# mapleCUx_med_024.net
KiCad netlist of a schematic drawn in EAGLE
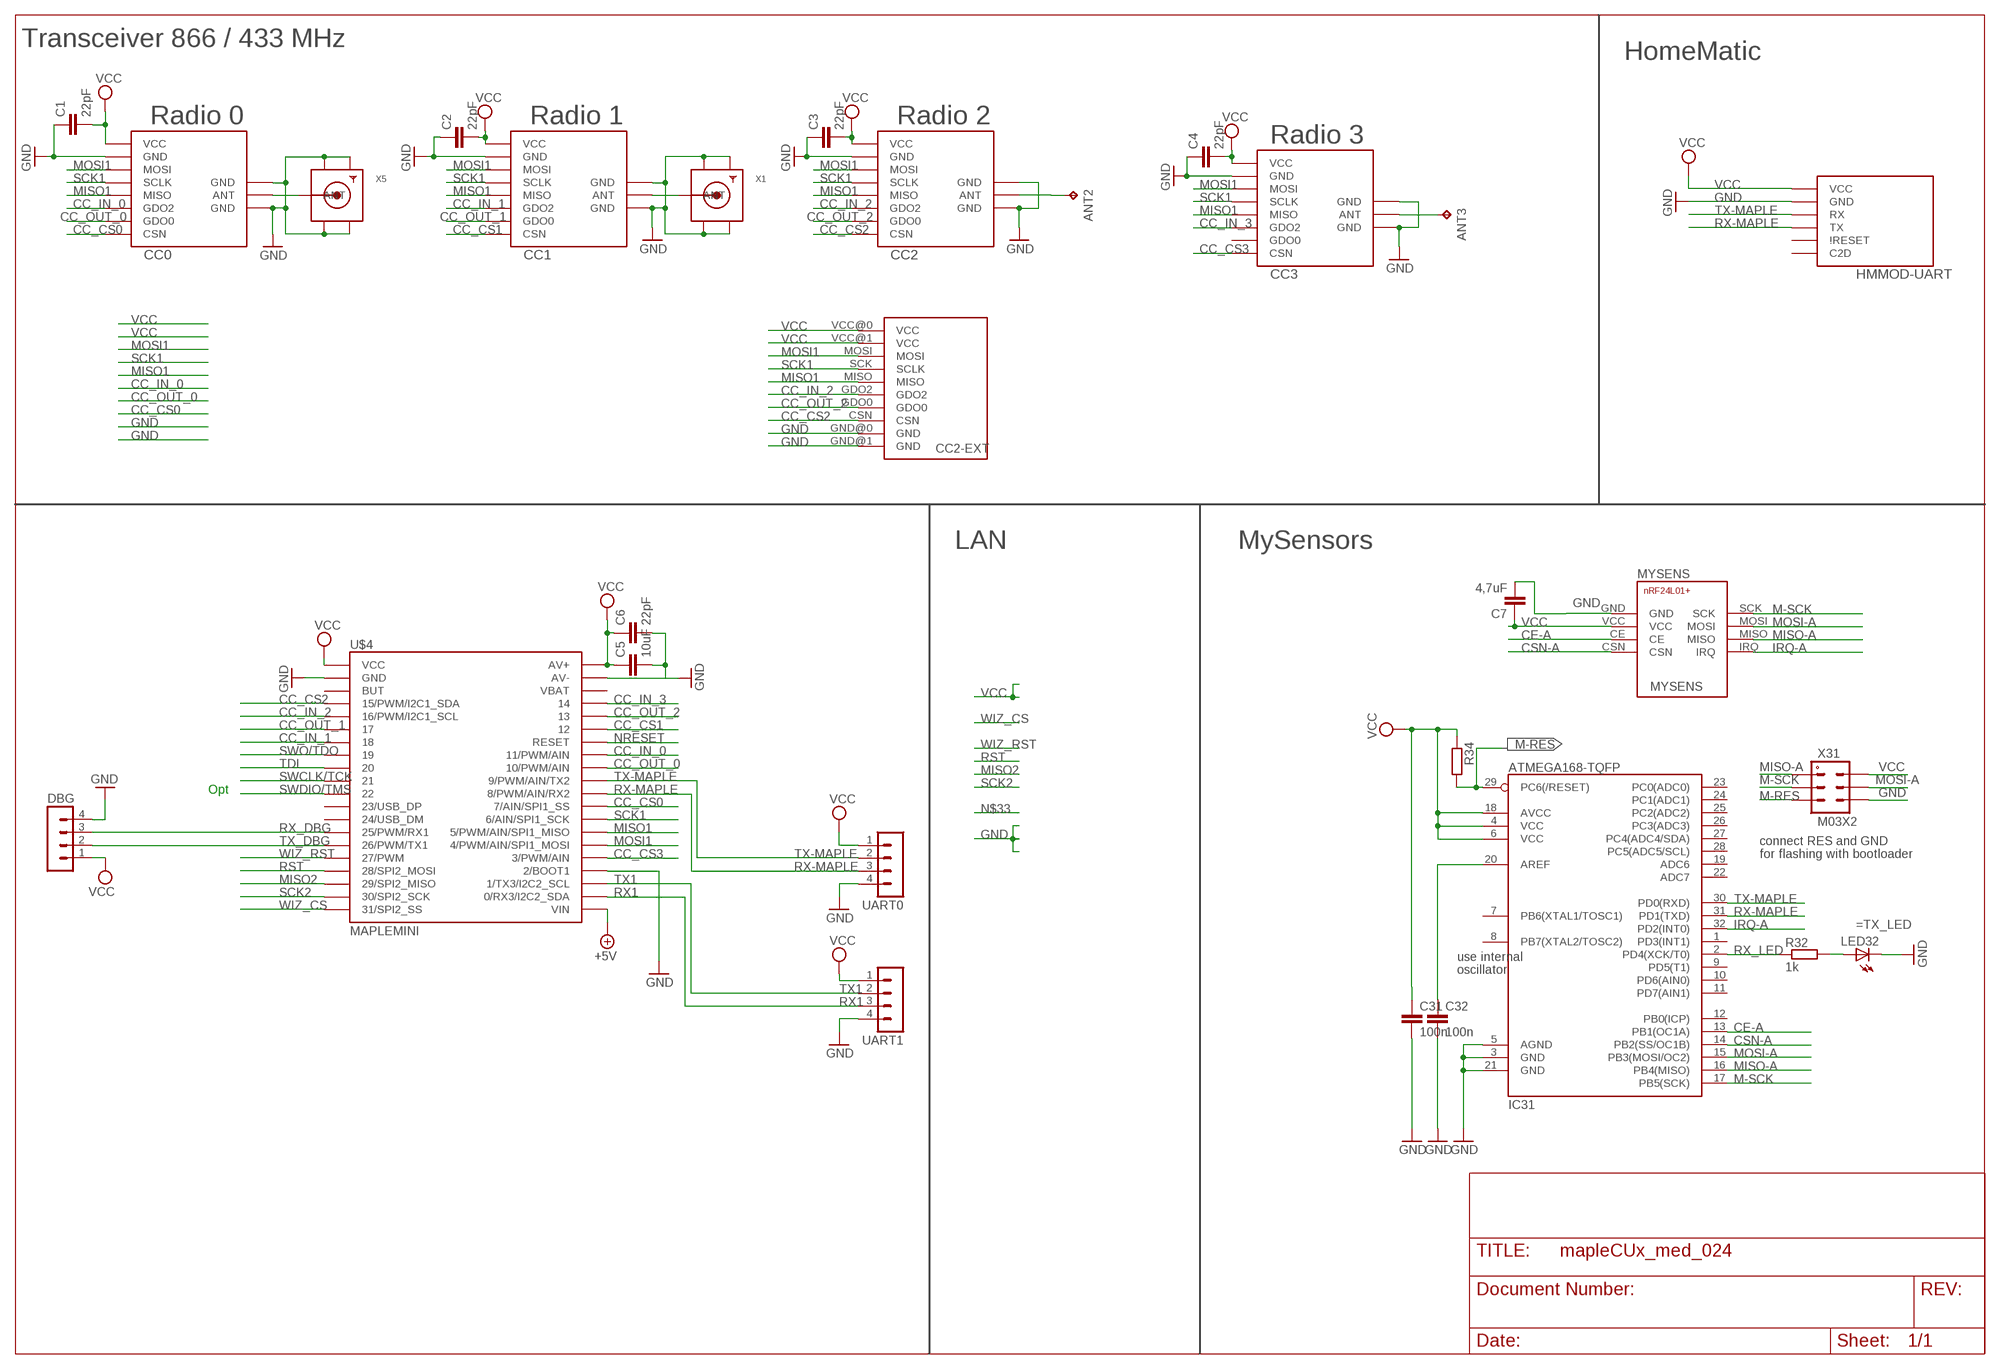
[diagram p0: schematic, sheet 1]

(export (version "E")
  (design (tool "Eeschema 10.0.6"))
  (components
    (comp (ref "ANT2")
      (value "TPPAD1-13")
      (footprint "eagle-import:P1-13")
      (libsource (lib "eagle-import") (part "TPPAD1-13"))
    )
    (comp (ref "ANT3")
      (value "TPPAD1-13")
      (footprint "eagle-import:P1-13")
      (libsource (lib "eagle-import") (part "TPPAD1-13"))
    )
    (comp (ref "C1")
      (value "22pF")
      (footprint "eagle-import:C0805")
      (libsource (lib "eagle-import") (part "C-EUC0805"))
    )
    (comp (ref "C2")
      (value "22pF")
      (footprint "eagle-import:C0805")
      (libsource (lib "eagle-import") (part "C-EUC0805"))
    )
    (comp (ref "C3")
      (value "22pF")
      (footprint "eagle-import:C0805")
      (libsource (lib "eagle-import") (part "C-EUC0805"))
    )
    (comp (ref "C4")
      (value "22pF")
      (footprint "eagle-import:C0805")
      (libsource (lib "eagle-import") (part "C-EUC0805"))
    )
    (comp (ref "C5")
      (value "10uF")
      (footprint "eagle-import:C1210")
      (libsource (lib "eagle-import") (part "C-EUC1210"))
    )
    (comp (ref "C6")
      (value "22pF")
      (footprint "eagle-import:C0805")
      (libsource (lib "eagle-import") (part "C-EUC0805"))
    )
    (comp (ref "C7")
      (value "4,7uF")
      (footprint "eagle-import:C1210")
      (libsource (lib "eagle-import") (part "C-EUC1210"))
    )
    (comp (ref "C31")
      (value "100n")
      (footprint "eagle-import:C0805")
      (libsource (lib "eagle-import") (part "C-EUC0805"))
    )
    (comp (ref "C32")
      (value "100n")
      (footprint "eagle-import:C0805")
      (libsource (lib "eagle-import") (part "C-EUC0805"))
    )
    (comp (ref "CC0")
      (value "CC1101")
      (footprint "eagle-import:CC1101_MODULE1_SMD")
      (libsource (lib "eagle-import") (part "CC1101_MODULE1SMD"))
    )
    (comp (ref "CC1")
      (value "CC1101_MODULE1SMD")
      (footprint "eagle-import:CC1101_MODULE1_SMD")
      (libsource (lib "eagle-import") (part "CC1101_MODULE1SMD"))
    )
    (comp (ref "CC2")
      (value "CC1101_MODULE1SMD")
      (footprint "eagle-import:CC1101_MODULE1_SMD")
      (libsource (lib "eagle-import") (part "CC1101_MODULE1SMD"))
    )
    (comp (ref "CC2-EXT")
      (value "CC1101_MODULE3_DIL")
      (footprint "eagle-import:CC1101_MODULE3_DIL")
      (libsource (lib "eagle-import") (part "CC1101_MODULE3_DIL"))
    )
    (comp (ref "CC3")
      (value "CC1101_MODULE1SMD")
      (footprint "eagle-import:CC1101_MODULE1_SMD")
      (libsource (lib "eagle-import") (part "CC1101_MODULE1SMD"))
    )
    (comp (ref "DBG")
      (value "MA04-1")
      (footprint "eagle-import:MA04-1")
      (libsource (lib "eagle-import") (part "MA04-1"))
    )
    (comp (ref "HMMOD-UART")
      (value "HM-MOD-UARTDIL")
      (footprint "eagle-import:HM-MOD-UART-DIL")
      (libsource (lib "eagle-import") (part "HM-MOD-UARTDIL"))
    )
    (comp (ref "IC31")
      (value "ATMEGA168-TQFP")
      (footprint "eagle-import:TQFP32-08")
      (libsource (lib "eagle-import") (part "ATMEGA168-TQFP"))
    )
    (comp (ref "LED32")
      (value "LEDCHIPLED_0805")
      (footprint "eagle-import:CHIPLED_0805")
      (libsource (lib "eagle-import") (part "LEDCHIPLED_0805"))
    )
    (comp (ref "MYSENS")
      (value "NRF24L01+SMD")
      (footprint "eagle-import:NRF24L01+SMD")
      (libsource (lib "eagle-import") (part "NRF24L01+SMD"))
    )
    (comp (ref "R32")
      (value "1k")
      (footprint "eagle-import:R0805")
      (libsource (lib "eagle-import") (part "R-EU_R0805"))
    )
    (comp (ref "R34")
      (value "R-EU_R0805")
      (footprint "eagle-import:R0805")
      (libsource (lib "eagle-import") (part "R-EU_R0805"))
    )
    (comp (ref "U$4")
      (value "MAPLEMINI")
      (footprint "eagle-import:20-DIP")
      (libsource (lib "eagle-import") (part "MAPLEMINI"))
    )
    (comp (ref "UART0")
      (value "MA04-1")
      (footprint "eagle-import:MA04-1")
      (libsource (lib "eagle-import") (part "MA04-1"))
    )
    (comp (ref "UART1")
      (value "MA04-1")
      (footprint "eagle-import:MA04-1")
      (libsource (lib "eagle-import") (part "MA04-1"))
    )
    (comp (ref "X1")
      (value "SMACONNECTOR_EDGE_UFL")
      (footprint "eagle-import:SMA_EDGELAUNCH_UFL")
      (libsource (lib "eagle-import") (part "SMACONNECTOR_EDGE_UFL"))
    )
    (comp (ref "X5")
      (value "SMACONNECTOR_EDGE_UFL")
      (footprint "eagle-import:SMA_EDGELAUNCH_UFL")
      (libsource (lib "eagle-import") (part "SMACONNECTOR_EDGE_UFL"))
    )
    (comp (ref "X31")
      (value "M03X2")
      (footprint "eagle-import:2X03-1.27MM_SMD")
      (libsource (lib "eagle-import") (part "M03X2"))
    )
  )
  (nets
    (net (code "1") (name "+5V") (class "Default")
      (node (ref "U$4") (pin "21") (pinfunction "VIN_21") (pintype "bidirectional"))
    )
    (net (code "2") (name "/CC_CS0") (class "Default")
      (node (ref "CC0") (pin "CSN") (pinfunction "CSN_CSN") (pintype "bidirectional"))
      (node (ref "U$4") (pin "29") (pinfunction "7/AIN/SPI1_SS_29") (pintype "bidirectional"))
    )
    (net (code "3") (name "/CC_CS1") (class "Default")
      (node (ref "CC1") (pin "CSN") (pinfunction "CSN_CSN") (pintype "bidirectional"))
      (node (ref "U$4") (pin "35") (pinfunction "12_35") (pintype "bidirectional"))
    )
    (net (code "4") (name "/CC_CS2") (class "Default")
      (node (ref "CC2") (pin "CSN") (pinfunction "CSN_CSN") (pintype "bidirectional"))
      (node (ref "CC2-EXT") (pin "CSN") (pinfunction "CSN_CSN") (pintype "bidirectional"))
      (node (ref "U$4") (pin "4") (pinfunction "15/PWM/I2C1_SDA_4") (pintype "bidirectional"))
    )
    (net (code "5") (name "/CC_CS3") (class "Default")
      (node (ref "CC3") (pin "CSN") (pinfunction "CSN_CSN") (pintype "bidirectional"))
      (node (ref "U$4") (pin "25") (pinfunction "3/PWM/AIN_25") (pintype "bidirectional"))
    )
    (net (code "6") (name "/CC_IN_0") (class "Default")
      (node (ref "CC0") (pin "GDO2") (pinfunction "GDO2_GDO2") (pintype "bidirectional"))
      (node (ref "U$4") (pin "33") (pinfunction "11/PWM/AIN_33") (pintype "bidirectional"))
    )
    (net (code "7") (name "/CC_IN_1") (class "Default")
      (node (ref "CC1") (pin "GDO2") (pinfunction "GDO2_GDO2") (pintype "bidirectional"))
      (node (ref "U$4") (pin "7") (pinfunction "18_7") (pintype "bidirectional"))
    )
    (net (code "8") (name "/CC_IN_2") (class "Default")
      (node (ref "CC2") (pin "GDO2") (pinfunction "GDO2_GDO2") (pintype "bidirectional"))
      (node (ref "CC2-EXT") (pin "GDO2") (pinfunction "GDO2_GDO2") (pintype "bidirectional"))
      (node (ref "U$4") (pin "5") (pinfunction "16/PWM/I2C1_SCL_5") (pintype "bidirectional"))
    )
    (net (code "9") (name "/CC_IN_3") (class "Default")
      (node (ref "CC3") (pin "GDO2") (pinfunction "GDO2_GDO2") (pintype "bidirectional"))
      (node (ref "U$4") (pin "37") (pinfunction "14_37") (pintype "bidirectional"))
    )
    (net (code "10") (name "/CC_OUT_0") (class "Default")
      (node (ref "CC0") (pin "GDO0") (pinfunction "GDO0_GDO0") (pintype "bidirectional"))
      (node (ref "U$4") (pin "32") (pinfunction "10/PWM/AIN_32") (pintype "bidirectional"))
    )
    (net (code "11") (name "/CC_OUT_1") (class "Default")
      (node (ref "CC1") (pin "GDO0") (pinfunction "GDO0_GDO0") (pintype "bidirectional"))
      (node (ref "U$4") (pin "6") (pinfunction "17_6") (pintype "bidirectional"))
    )
    (net (code "12") (name "/CC_OUT_2") (class "Default")
      (node (ref "CC2") (pin "GDO0") (pinfunction "GDO0_GDO0") (pintype "bidirectional"))
      (node (ref "CC2-EXT") (pin "GDO0") (pinfunction "GDO0_GDO0") (pintype "bidirectional"))
      (node (ref "U$4") (pin "36") (pinfunction "13_36") (pintype "bidirectional"))
    )
    (net (code "13") (name "/CE-A") (class "Default")
      (node (ref "IC31") (pin "13") (pinfunction "PB1(OC1A)_13") (pintype "bidirectional"))
      (node (ref "MYSENS") (pin "CE") (pinfunction "CE_CE") (pintype "bidirectional"))
    )
    (net (code "14") (name "/CSN-A") (class "Default")
      (node (ref "IC31") (pin "14") (pinfunction "PB2(SS/OC1B)_14") (pintype "bidirectional"))
      (node (ref "MYSENS") (pin "CSN") (pinfunction "CSN_CSN") (pintype "bidirectional"))
    )
    (net (code "15") (name "/IRQ-A") (class "Default")
      (node (ref "IC31") (pin "32") (pinfunction "PD2(INT0)_32") (pintype "bidirectional"))
      (node (ref "MYSENS") (pin "IRQ") (pinfunction "IRQ_IRQ") (pintype "bidirectional"))
    )
    (net (code "16") (name "/M-RES") (class "Default")
      (node (ref "IC31") (pin "29") (pinfunction "PC6(/RESET)_29") (pintype "bidirectional"))
      (node (ref "R34") (pin "2") (pinfunction "2_2") (pintype "passive"))
      (node (ref "X31") (pin "P$5") (pinfunction "5_P$5") (pintype "passive"))
    )
    (net (code "17") (name "/M-SCK") (class "Default")
      (node (ref "IC31") (pin "17") (pinfunction "PB5(SCK)_17") (pintype "bidirectional"))
      (node (ref "MYSENS") (pin "SCK") (pinfunction "SCK_SCK") (pintype "bidirectional"))
      (node (ref "X31") (pin "P$3") (pinfunction "3_P$3") (pintype "passive"))
    )
    (net (code "18") (name "/MISO-A") (class "Default")
      (node (ref "IC31") (pin "16") (pinfunction "PB4(MISO)_16") (pintype "bidirectional"))
      (node (ref "MYSENS") (pin "MISO") (pinfunction "MISO_MISO") (pintype "bidirectional"))
      (node (ref "X31") (pin "P$1") (pinfunction "1_P$1") (pintype "passive"))
    )
    (net (code "19") (name "/MISO1") (class "Default")
      (node (ref "CC0") (pin "MISO") (pinfunction "MISO_MISO") (pintype "bidirectional"))
      (node (ref "CC1") (pin "MISO") (pinfunction "MISO_MISO") (pintype "bidirectional"))
      (node (ref "CC2") (pin "MISO") (pinfunction "MISO_MISO") (pintype "bidirectional"))
      (node (ref "CC2-EXT") (pin "MISO") (pinfunction "MISO_MISO") (pintype "bidirectional"))
      (node (ref "CC3") (pin "MISO") (pinfunction "MISO_MISO") (pintype "bidirectional"))
      (node (ref "U$4") (pin "27") (pinfunction "5/PWM/AIN/SPI1_MISO_27") (pintype "bidirectional"))
    )
    (net (code "20") (name "/MISO2") (class "Default")
      (node (ref "U$4") (pin "18") (pinfunction "29/SPI2_MISO_18") (pintype "bidirectional"))
    )
    (net (code "21") (name "/MOSI-A") (class "Default")
      (node (ref "IC31") (pin "15") (pinfunction "PB3(MOSI/OC2)_15") (pintype "bidirectional"))
      (node (ref "MYSENS") (pin "MOSI") (pinfunction "MOSI_MOSI") (pintype "bidirectional"))
      (node (ref "X31") (pin "P$4") (pinfunction "4_P$4") (pintype "passive"))
    )
    (net (code "22") (name "/MOSI1") (class "Default")
      (node (ref "CC0") (pin "MOSI") (pinfunction "MOSI_MOSI") (pintype "bidirectional"))
      (node (ref "CC1") (pin "MOSI") (pinfunction "MOSI_MOSI") (pintype "bidirectional"))
      (node (ref "CC2") (pin "MOSI") (pinfunction "MOSI_MOSI") (pintype "bidirectional"))
      (node (ref "CC2-EXT") (pin "MOSI") (pinfunction "MOSI_MOSI") (pintype "bidirectional"))
      (node (ref "CC3") (pin "MOSI") (pinfunction "MOSI_MOSI") (pintype "bidirectional"))
      (node (ref "U$4") (pin "26") (pinfunction "4/PWM/AIN/SPI1_MOSI_26") (pintype "bidirectional"))
    )
    (net (code "24") (name "/NRESET") (class "Default")
      (node (ref "U$4") (pin "34") (pinfunction "RESET_34") (pintype "bidirectional"))
    )
    (net (code "25") (name "/RST") (class "Default")
      (node (ref "U$4") (pin "17") (pinfunction "28/SPI2_MOSI_17") (pintype "bidirectional"))
    )
    (net (code "26") (name "/RX-MAPLE") (class "Default")
      (node (ref "HMMOD-UART") (pin "5") (pinfunction "TX_5") (pintype "bidirectional"))
      (node (ref "IC31") (pin "31") (pinfunction "PD1(TXD)_31") (pintype "bidirectional"))
      (node (ref "U$4") (pin "30") (pinfunction "8/PWM/AIN/RX2_30") (pintype "bidirectional"))
      (node (ref "UART0") (pin "3") (pinfunction "3_3") (pintype "passive"))
    )
    (net (code "27") (name "/RX1") (class "Default")
      (node (ref "U$4") (pin "22") (pinfunction "0/RX3/I2C2_SDA_22") (pintype "bidirectional"))
      (node (ref "UART1") (pin "3") (pinfunction "3_3") (pintype "passive"))
    )
    (net (code "28") (name "/RX_DBG") (class "Default")
      (node (ref "DBG") (pin "3") (pinfunction "3_3") (pintype "passive"))
      (node (ref "U$4") (pin "14") (pinfunction "25/PWM/RX1_14") (pintype "bidirectional"))
    )
    (net (code "29") (name "/RX_LED") (class "Default")
      (node (ref "IC31") (pin "2") (pinfunction "PD4(XCK/T0)_2") (pintype "bidirectional"))
      (node (ref "R32") (pin "1") (pinfunction "1_1") (pintype "passive"))
    )
    (net (code "30") (name "/SCK1") (class "Default")
      (node (ref "CC0") (pin "SCLK") (pinfunction "SCLK_SCLK") (pintype "bidirectional"))
      (node (ref "CC1") (pin "SCLK") (pinfunction "SCLK_SCLK") (pintype "bidirectional"))
      (node (ref "CC2") (pin "SCLK") (pinfunction "SCLK_SCLK") (pintype "bidirectional"))
      (node (ref "CC2-EXT") (pin "SCK") (pinfunction "SCLK_SCK") (pintype "bidirectional"))
      (node (ref "CC3") (pin "SCLK") (pinfunction "SCLK_SCLK") (pintype "bidirectional"))
      (node (ref "U$4") (pin "28") (pinfunction "6/AIN/SPI1_SCK_28") (pintype "bidirectional"))
    )
    (net (code "31") (name "/SCK2") (class "Default")
      (node (ref "U$4") (pin "19") (pinfunction "30/SPI2_SCK_19") (pintype "bidirectional"))
    )
    (net (code "32") (name "/SWCLK{slash}TCK") (class "Default")
      (node (ref "U$4") (pin "10") (pinfunction "21_10") (pintype "bidirectional"))
    )
    (net (code "33") (name "/SWDIO{slash}TMS") (class "Default")
      (node (ref "U$4") (pin "11") (pinfunction "22_11") (pintype "bidirectional"))
    )
    (net (code "34") (name "/SWO{slash}TDO") (class "Default")
      (node (ref "U$4") (pin "8") (pinfunction "19_8") (pintype "bidirectional"))
    )
    (net (code "35") (name "/TDI") (class "Default")
      (node (ref "U$4") (pin "9") (pinfunction "20_9") (pintype "bidirectional"))
    )
    (net (code "36") (name "/TX-MAPLE") (class "Default")
      (node (ref "HMMOD-UART") (pin "6") (pinfunction "RX_6") (pintype "bidirectional"))
      (node (ref "IC31") (pin "30") (pinfunction "PD0(RXD)_30") (pintype "bidirectional"))
      (node (ref "U$4") (pin "31") (pinfunction "9/PWM/AIN/TX2_31") (pintype "bidirectional"))
      (node (ref "UART0") (pin "2") (pinfunction "2_2") (pintype "passive"))
    )
    (net (code "37") (name "/TX1") (class "Default")
      (node (ref "U$4") (pin "23") (pinfunction "1/TX3/I2C2_SCL_23") (pintype "bidirectional"))
      (node (ref "UART1") (pin "2") (pinfunction "2_2") (pintype "passive"))
    )
    (net (code "38") (name "/TX_DBG") (class "Default")
      (node (ref "DBG") (pin "2") (pinfunction "2_2") (pintype "passive"))
      (node (ref "U$4") (pin "15") (pinfunction "26/PWM/TX1_15") (pintype "bidirectional"))
    )
    (net (code "39") (name "/WIZ_CS") (class "Default")
      (node (ref "U$4") (pin "20") (pinfunction "31/SPI2_SS_20") (pintype "bidirectional"))
    )
    (net (code "40") (name "/WIZ_RST") (class "Default")
      (node (ref "U$4") (pin "16") (pinfunction "27/PWM_16") (pintype "bidirectional"))
    )
    (net (code "41") (name "GND") (class "Default")
      (node (ref "C1") (pin "1") (pinfunction "1_1") (pintype "passive"))
      (node (ref "C2") (pin "1") (pinfunction "1_1") (pintype "passive"))
      (node (ref "C3") (pin "1") (pinfunction "1_1") (pintype "passive"))
      (node (ref "C31") (pin "2") (pinfunction "2_2") (pintype "passive"))
      (node (ref "C32") (pin "2") (pinfunction "2_2") (pintype "passive"))
      (node (ref "C4") (pin "1") (pinfunction "1_1") (pintype "passive"))
      (node (ref "C5") (pin "2") (pinfunction "2_2") (pintype "passive"))
      (node (ref "C6") (pin "2") (pinfunction "2_2") (pintype "passive"))
      (node (ref "C7") (pin "2") (pinfunction "2_2") (pintype "passive"))
      (node (ref "CC0") (pin "GND@0") (pinfunction "GND_GND@0") (pintype "power_in"))
      (node (ref "CC0") (pin "GND@1") (pinfunction "GND_GND@1") (pintype "power_in"))
      (node (ref "CC0") (pin "GND@2") (pinfunction "GND_GND@2") (pintype "power_in"))
      (node (ref "CC1") (pin "GND@0") (pinfunction "GND_GND@0") (pintype "power_in"))
      (node (ref "CC1") (pin "GND@1") (pinfunction "GND_GND@1") (pintype "power_in"))
      (node (ref "CC1") (pin "GND@2") (pinfunction "GND_GND@2") (pintype "power_in"))
      (node (ref "CC2") (pin "GND@0") (pinfunction "GND_GND@0") (pintype "power_in"))
      (node (ref "CC2") (pin "GND@1") (pinfunction "GND_GND@1") (pintype "power_in"))
      (node (ref "CC2") (pin "GND@2") (pinfunction "GND_GND@2") (pintype "power_in"))
      (node (ref "CC2-EXT") (pin "GND@0") (pinfunction "GND_GND@0") (pintype "power_in"))
      (node (ref "CC2-EXT") (pin "GND@1") (pinfunction "GND_GND@1") (pintype "power_in"))
      (node (ref "CC3") (pin "GND@0") (pinfunction "GND_GND@0") (pintype "power_in"))
      (node (ref "CC3") (pin "GND@1") (pinfunction "GND_GND@1") (pintype "power_in"))
      (node (ref "CC3") (pin "GND@2") (pinfunction "GND_GND@2") (pintype "power_in"))
      (node (ref "DBG") (pin "4") (pinfunction "4_4") (pintype "passive"))
      (node (ref "HMMOD-UART") (pin "2") (pinfunction "GND_2") (pintype "power_in"))
      (node (ref "IC31") (pin "21") (pinfunction "GND_21") (pintype "bidirectional"))
      (node (ref "IC31") (pin "3") (pinfunction "GND_3") (pintype "bidirectional"))
      (node (ref "IC31") (pin "5") (pinfunction "AGND_5") (pintype "bidirectional"))
      (node (ref "LED32") (pin "C") (pinfunction "C_C") (pintype "passive"))
      (node (ref "MYSENS") (pin "GND") (pinfunction "GND_GND") (pintype "power_in"))
      (node (ref "U$4") (pin "2") (pinfunction "GND_2") (pintype "bidirectional"))
      (node (ref "U$4") (pin "24") (pinfunction "2/BOOT1_24") (pintype "bidirectional"))
      (node (ref "U$4") (pin "39") (pinfunction "AV-_39") (pintype "bidirectional"))
      (node (ref "UART0") (pin "4") (pinfunction "4_4") (pintype "passive"))
      (node (ref "UART1") (pin "4") (pinfunction "4_4") (pintype "passive"))
      (node (ref "X1") (pin "GND@1") (pinfunction "GND1_GND@1") (pintype "power_in"))
      (node (ref "X1") (pin "GND@2") (pinfunction "GND2_GND@2") (pintype "power_in"))
      (node (ref "X1") (pin "GND@3") (pinfunction "GND3_GND@3") (pintype "power_in"))
      (node (ref "X1") (pin "GND@4") (pinfunction "GND4_GND@4") (pintype "power_in"))
      (node (ref "X31") (pin "P$6") (pinfunction "6_P$6") (pintype "passive"))
      (node (ref "X5") (pin "GND@1") (pinfunction "GND1_GND@1") (pintype "power_in"))
      (node (ref "X5") (pin "GND@2") (pinfunction "GND2_GND@2") (pintype "power_in"))
      (node (ref "X5") (pin "GND@3") (pinfunction "GND3_GND@3") (pintype "power_in"))
      (node (ref "X5") (pin "GND@4") (pinfunction "GND4_GND@4") (pintype "power_in"))
    )
    (net (code "42") (name "Net-(ANT2-PadTP)") (class "Default")
      (node (ref "ANT2") (pin "TP") (pinfunction "TP_TP") (pintype "input"))
      (node (ref "CC2") (pin "ANT") (pinfunction "ANT_ANT") (pintype "output"))
    )
    (net (code "43") (name "Net-(ANT3-PadTP)") (class "Default")
      (node (ref "ANT3") (pin "TP") (pinfunction "TP_TP") (pintype "input"))
      (node (ref "CC3") (pin "ANT") (pinfunction "ANT_ANT") (pintype "output"))
    )
    (net (code "44") (name "Net-(IC31-AREF)") (class "Default")
      (node (ref "C32") (pin "1") (pinfunction "1_1") (pintype "passive"))
      (node (ref "IC31") (pin "20") (pinfunction "AREF_20") (pintype "bidirectional"))
    )
    (net (code "45") (name "Net-(LED32-PadA)") (class "Default")
      (node (ref "LED32") (pin "A") (pinfunction "A_A") (pintype "passive"))
      (node (ref "R32") (pin "2") (pinfunction "2_2") (pintype "passive"))
    )
    (net (code "46") (name "Net-(X1-ANT)") (class "Default")
      (node (ref "CC1") (pin "ANT") (pinfunction "ANT_ANT") (pintype "output"))
      (node (ref "X1") (pin "P") (pinfunction "ANT_P") (pintype "bidirectional"))
    )
    (net (code "47") (name "Net-(X5-ANT)") (class "Default")
      (node (ref "CC0") (pin "ANT") (pinfunction "ANT_ANT") (pintype "output"))
      (node (ref "X5") (pin "P") (pinfunction "ANT_P") (pintype "bidirectional"))
    )
    (net (code "48") (name "VCC") (class "Default")
      (node (ref "C1") (pin "2") (pinfunction "2_2") (pintype "passive"))
      (node (ref "C2") (pin "2") (pinfunction "2_2") (pintype "passive"))
      (node (ref "C3") (pin "2") (pinfunction "2_2") (pintype "passive"))
      (node (ref "C31") (pin "1") (pinfunction "1_1") (pintype "passive"))
      (node (ref "C4") (pin "2") (pinfunction "2_2") (pintype "passive"))
      (node (ref "C5") (pin "1") (pinfunction "1_1") (pintype "passive"))
      (node (ref "C6") (pin "1") (pinfunction "1_1") (pintype "passive"))
      (node (ref "C7") (pin "1") (pinfunction "1_1") (pintype "passive"))
      (node (ref "CC0") (pin "VCC") (pinfunction "VCC_VCC") (pintype "power_in"))
      (node (ref "CC1") (pin "VCC") (pinfunction "VCC_VCC") (pintype "power_in"))
      (node (ref "CC2") (pin "VCC") (pinfunction "VCC_VCC") (pintype "power_in"))
      (node (ref "CC2-EXT") (pin "VCC@0") (pinfunction "VCC_VCC@0") (pintype "power_in"))
      (node (ref "CC2-EXT") (pin "VCC@1") (pinfunction "VCC_VCC@1") (pintype "power_in"))
      (node (ref "CC3") (pin "VCC") (pinfunction "VCC_VCC") (pintype "power_in"))
      (node (ref "DBG") (pin "1") (pinfunction "1_1") (pintype "passive"))
      (node (ref "HMMOD-UART") (pin "1") (pinfunction "VCC_1") (pintype "power_in"))
      (node (ref "IC31") (pin "18") (pinfunction "AVCC_18") (pintype "bidirectional"))
      (node (ref "IC31") (pin "4") (pinfunction "VCC_4") (pintype "bidirectional"))
      (node (ref "IC31") (pin "6") (pinfunction "VCC_6") (pintype "bidirectional"))
      (node (ref "MYSENS") (pin "VCC") (pinfunction "VCC_VCC") (pintype "power_in"))
      (node (ref "R34") (pin "1") (pinfunction "1_1") (pintype "passive"))
      (node (ref "U$4") (pin "1") (pinfunction "VCC_1") (pintype "bidirectional"))
      (node (ref "U$4") (pin "40") (pinfunction "AV+_40") (pintype "bidirectional"))
      (node (ref "UART0") (pin "1") (pinfunction "1_1") (pintype "passive"))
      (node (ref "UART1") (pin "1") (pinfunction "1_1") (pintype "passive"))
      (node (ref "X31") (pin "P$2") (pinfunction "2_P$2") (pintype "passive"))
    )
    (net (code "49") (name "unconnected-(CC3-PadGDO0)") (class "Default")
      (node (ref "CC3") (pin "GDO0") (pinfunction "GDO0_GDO0") (pintype "bidirectional"))
    )
    (net (code "50") (name "unconnected-(HMMOD-UART-C2D-Pad3)") (class "Default")
      (node (ref "HMMOD-UART") (pin "3") (pinfunction "C2D_3") (pintype "bidirectional"))
    )
    (net (code "51") (name "unconnected-(HMMOD-UART-\\~{RESET}-Pad4)") (class "Default")
      (node (ref "HMMOD-UART") (pin "4") (pinfunction "\\~{RESET}_4") (pintype "bidirectional"))
    )
    (net (code "52") (name "unconnected-(IC31-ADC6-Pad19)") (class "Default")
      (node (ref "IC31") (pin "19") (pinfunction "ADC6_19") (pintype "bidirectional"))
    )
    (net (code "53") (name "unconnected-(IC31-ADC7-Pad22)") (class "Default")
      (node (ref "IC31") (pin "22") (pinfunction "ADC7_22") (pintype "bidirectional"))
    )
    (net (code "54") (name "unconnected-(IC31-PB0(ICP)-Pad12)") (class "Default")
      (node (ref "IC31") (pin "12") (pinfunction "PB0(ICP)_12") (pintype "bidirectional"))
    )
    (net (code "55") (name "unconnected-(IC31-PB6(XTAL1{slash}TOSC1)-Pad7)") (class "Default")
      (node (ref "IC31") (pin "7") (pinfunction "PB6(XTAL1/TOSC1)_7") (pintype "bidirectional"))
    )
    (net (code "56") (name "unconnected-(IC31-PB7(XTAL2{slash}TOSC2)-Pad8)") (class "Default")
      (node (ref "IC31") (pin "8") (pinfunction "PB7(XTAL2/TOSC2)_8") (pintype "bidirectional"))
    )
    (net (code "57") (name "unconnected-(IC31-PC0(ADC0)-Pad23)") (class "Default")
      (node (ref "IC31") (pin "23") (pinfunction "PC0(ADC0)_23") (pintype "bidirectional"))
    )
    (net (code "58") (name "unconnected-(IC31-PC1(ADC1)-Pad24)") (class "Default")
      (node (ref "IC31") (pin "24") (pinfunction "PC1(ADC1)_24") (pintype "bidirectional"))
    )
    (net (code "59") (name "unconnected-(IC31-PC2(ADC2)-Pad25)") (class "Default")
      (node (ref "IC31") (pin "25") (pinfunction "PC2(ADC2)_25") (pintype "bidirectional"))
    )
    (net (code "60") (name "unconnected-(IC31-PC3(ADC3)-Pad26)") (class "Default")
      (node (ref "IC31") (pin "26") (pinfunction "PC3(ADC3)_26") (pintype "bidirectional"))
    )
    (net (code "61") (name "unconnected-(IC31-PC4(ADC4{slash}SDA)-Pad27)") (class "Default")
      (node (ref "IC31") (pin "27") (pinfunction "PC4(ADC4/SDA)_27") (pintype "bidirectional"))
    )
    (net (code "62") (name "unconnected-(IC31-PC5(ADC5{slash}SCL)-Pad28)") (class "Default")
      (node (ref "IC31") (pin "28") (pinfunction "PC5(ADC5/SCL)_28") (pintype "bidirectional"))
    )
    (net (code "63") (name "unconnected-(IC31-PD3(INT1)-Pad1)") (class "Default")
      (node (ref "IC31") (pin "1") (pinfunction "PD3(INT1)_1") (pintype "bidirectional"))
    )
    (net (code "64") (name "unconnected-(IC31-PD5(T1)-Pad9)") (class "Default")
      (node (ref "IC31") (pin "9") (pinfunction "PD5(T1)_9") (pintype "bidirectional"))
    )
    (net (code "65") (name "unconnected-(IC31-PD6(AIN0)-Pad10)") (class "Default")
      (node (ref "IC31") (pin "10") (pinfunction "PD6(AIN0)_10") (pintype "bidirectional"))
    )
    (net (code "66") (name "unconnected-(IC31-PD7(AIN1)-Pad11)") (class "Default")
      (node (ref "IC31") (pin "11") (pinfunction "PD7(AIN1)_11") (pintype "bidirectional"))
    )
    (net (code "67") (name "unconnected-(U$4-23{slash}USB_DP-Pad12)") (class "Default")
      (node (ref "U$4") (pin "12") (pinfunction "23/USB_DP_12") (pintype "bidirectional"))
    )
    (net (code "68") (name "unconnected-(U$4-24{slash}USB_DM-Pad13)") (class "Default")
      (node (ref "U$4") (pin "13") (pinfunction "24/USB_DM_13") (pintype "bidirectional"))
    )
    (net (code "69") (name "unconnected-(U$4-BUT-Pad3)") (class "Default")
      (node (ref "U$4") (pin "3") (pinfunction "BUT_3") (pintype "bidirectional"))
    )
    (net (code "70") (name "unconnected-(U$4-VBAT-Pad38)") (class "Default")
      (node (ref "U$4") (pin "38") (pinfunction "VBAT_38") (pintype "bidirectional"))
    )
  )
)
